# design.net
KiCad netlist of a schematic drawn in Altium Designer
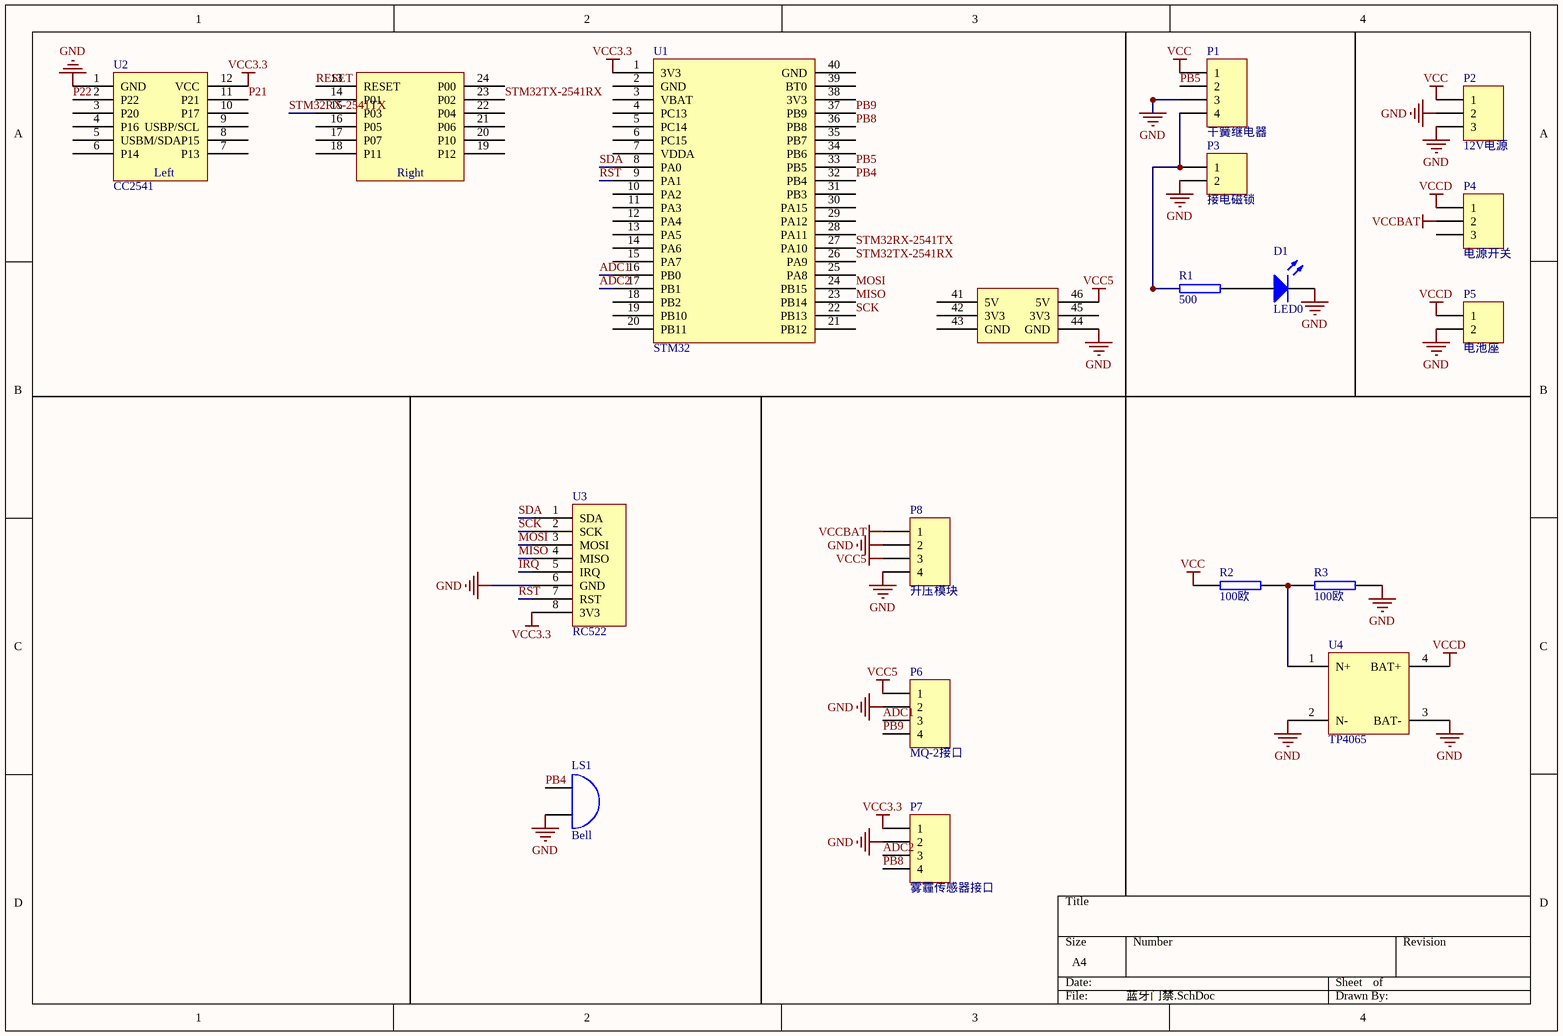
[diagram p0: 蓝牙门禁.SchDoc]

(export (version "E")
  (design (tool "Eeschema 10.0.6"))
  (components
    (comp (ref "D1")
      (value "LED0")
      (footprint "0805-led")
      (description "Typical INFRARED GaAs LED")
      (fields (field (name "PUBLISHER") "Altium Limited"))
      (libsource (lib "Miscellaneous Devices") (part "LED0"))
    )
    (comp (ref "LS1")
      (value "Bell")
      (footprint "BUZZER-12MM")
      (description "Electrical Bell")
      (fields (field (name "PUBLISHER") "Altium Limited"))
      (libsource (lib "Miscellaneous Devices") (part "Bell"))
    )
    (comp (ref "P1")
      (value "干簧继电器")
      (footprint "干簧继电器SIP-1A05")
      (description "Header, 4-Pin")
      (fields (field (name "PUBLISHER") "Altium Limited"))
      (libsource (lib "Miscellaneous Connectors") (part "Header 4"))
    )
    (comp (ref "P2")
      (value "12V电源")
      (footprint "DC-005(5.5MM)")
      (description "Header, 3-Pin")
      (fields (field (name "PUBLISHER") "Altium Limited"))
      (libsource (lib "Miscellaneous Connectors") (part "Header 3"))
    )
    (comp (ref "P3")
      (value "接电磁锁")
      (footprint "接线端子-0.5")
      (description "Header, 2-Pin, Right Angle")
      (fields (field (name "PUBLISHER") "Altium Limited"))
      (libsource (lib "Miscellaneous Connectors") (part "Header 2H"))
    )
    (comp (ref "P4")
      (value "电源开关")
      (footprint "拨动开关（2mm）")
      (description "Header, 3-Pin")
      (fields (field (name "PUBLISHER") "Altium Limited"))
      (libsource (lib "Miscellaneous Connectors") (part "Header 3"))
    )
    (comp (ref "P5")
      (value "电池座")
      (footprint "7号电池盒-4.5CM")
      (description "Header, 2-Pin")
      (fields (field (name "PUBLISHER") "Altium Limited"))
      (libsource (lib "Miscellaneous Connectors") (part "Header 2"))
    )
    (comp (ref "P6")
      (value "MQ-2接口")
      (footprint "HDR1X4")
      (description "Header, 4-Pin")
      (fields (field (name "PUBLISHER") "Altium Limited"))
      (libsource (lib "Miscellaneous Connectors") (part "Header 4"))
    )
    (comp (ref "P7")
      (value "雾霾传感器接口")
      (footprint "HDR1X4")
      (description "Header, 4-Pin")
      (fields (field (name "PUBLISHER") "Altium Limited"))
      (libsource (lib "Miscellaneous Connectors") (part "Header 4"))
    )
    (comp (ref "P8")
      (value "升压模块")
      (footprint "DC-DC升压模块")
      (description "Header, 4-Pin")
      (fields (field (name "PUBLISHER") "Altium Limited"))
      (libsource (lib "Miscellaneous Connectors") (part "Header 4"))
    )
    (comp (ref "R1") (value "500") (footprint "0805-SMALL") (libsource (lib "CC254xEM原理图库") (part "RES2")))
    (comp (ref "R2") (value "100欧") (footprint "0805-SMALL") (libsource (lib "CC254xEM原理图库") (part "RES2")))
    (comp (ref "R3") (value "100欧") (footprint "0805-SMALL") (libsource (lib "CC254xEM原理图库") (part "RES2")))
    (comp (ref "U1") (value "STM32") (footprint "STM32_Smart") (libsource (lib "我的原理图") (part "STM32_Smart")))
    (comp (ref "U2")
      (value "CC2541")
      (footprint "Smart_RF_2541")
      (libsource (lib "我的原理图") (part "Smart_RF_2541"))
    )
    (comp (ref "U3") (value "RC522") (footprint "HDR1X8") (libsource (lib "我的原理图") (part "RFID_RC522")))
    (comp (ref "U4") (value "TP4065") (footprint "TP4065_模块") (libsource (lib "我的原理图") (part "TP4056_ 模块")))
  )
  (nets
    (net (code "1") (name "/ADC1") (class "Default")
      (node (ref "P6") (pin "3") (pinfunction "3_3") (pintype "passive"))
      (node (ref "U1") (pin "16") (pinfunction "PB0_16") (pintype "passive"))
    )
    (net (code "2") (name "/ADC2") (class "Default")
      (node (ref "P7") (pin "3") (pinfunction "3_3") (pintype "passive"))
      (node (ref "U1") (pin "17") (pinfunction "PB1_17") (pintype "passive"))
    )
    (net (code "3") (name "/IRQ") (class "Default")
      (node (ref "U3") (pin "5") (pinfunction "IRQ_5") (pintype "passive"))
    )
    (net (code "4") (name "/MISO") (class "Default")
      (node (ref "U1") (pin "23") (pinfunction "PB14_23") (pintype "passive"))
      (node (ref "U3") (pin "4") (pinfunction "MISO_4") (pintype "passive"))
    )
    (net (code "5") (name "/MOSI") (class "Default")
      (node (ref "U1") (pin "24") (pinfunction "PB15_24") (pintype "passive"))
      (node (ref "U3") (pin "3") (pinfunction "MOSI_3") (pintype "passive"))
    )
    (net (code "6") (name "/P21") (class "Default")
      (node (ref "U2") (pin "11") (pinfunction "P21_11") (pintype "passive"))
    )
    (net (code "7") (name "/P22") (class "Default")
      (node (ref "U2") (pin "2") (pinfunction "P22_2") (pintype "passive"))
    )
    (net (code "8") (name "/PB4") (class "Default")
      (node (ref "LS1") (pin "1") (pinfunction "A_1") (pintype "passive"))
      (node (ref "U1") (pin "32") (pinfunction "PB4_32") (pintype "passive"))
    )
    (net (code "9") (name "/PB5") (class "Default")
      (node (ref "P1") (pin "2") (pinfunction "2_2") (pintype "passive"))
      (node (ref "U1") (pin "33") (pinfunction "PB5_33") (pintype "passive"))
    )
    (net (code "10") (name "/PB8") (class "Default")
      (node (ref "P7") (pin "4") (pinfunction "4_4") (pintype "passive"))
      (node (ref "U1") (pin "36") (pinfunction "PB8_36") (pintype "passive"))
    )
    (net (code "11") (name "/PB9") (class "Default")
      (node (ref "P6") (pin "4") (pinfunction "4_4") (pintype "passive"))
      (node (ref "U1") (pin "37") (pinfunction "PB9_37") (pintype "passive"))
    )
    (net (code "12") (name "/RESET") (class "Default")
      (node (ref "U2") (pin "13") (pinfunction "RESET_13") (pintype "passive"))
    )
    (net (code "13") (name "/RST") (class "Default")
      (node (ref "U1") (pin "9") (pinfunction "PA1_9") (pintype "passive"))
      (node (ref "U3") (pin "7") (pinfunction "RST_7") (pintype "passive"))
    )
    (net (code "14") (name "/SCK") (class "Default")
      (node (ref "U1") (pin "22") (pinfunction "PB13_22") (pintype "passive"))
      (node (ref "U3") (pin "2") (pinfunction "SCK_2") (pintype "passive"))
    )
    (net (code "15") (name "/SDA") (class "Default")
      (node (ref "U1") (pin "8") (pinfunction "PA0_8") (pintype "passive"))
      (node (ref "U3") (pin "1") (pinfunction "SDA_1") (pintype "passive"))
    )
    (net (code "16") (name "/STM32RX-2541TX") (class "Default")
      (node (ref "U1") (pin "27") (pinfunction "PA10_27") (pintype "passive"))
      (node (ref "U2") (pin "15") (pinfunction "P03_15") (pintype "passive"))
    )
    (net (code "17") (name "/STM32TX-2541RX") (class "Default")
      (node (ref "U1") (pin "26") (pinfunction "PA9_26") (pintype "passive"))
      (node (ref "U2") (pin "23") (pinfunction "P02_23") (pintype "passive"))
    )
    (net (code "18") (name "GND") (class "Default")
      (node (ref "D1") (pin "2") (pinfunction "K_2") (pintype "passive"))
      (node (ref "LS1") (pin "2") (pinfunction "B_2") (pintype "passive"))
      (node (ref "P1") (pin "3") (pinfunction "3_3") (pintype "passive"))
      (node (ref "P2") (pin "2") (pinfunction "2_2") (pintype "passive"))
      (node (ref "P2") (pin "3") (pinfunction "3_3") (pintype "passive"))
      (node (ref "P3") (pin "2") (pinfunction "2_2") (pintype "passive"))
      (node (ref "P5") (pin "2") (pinfunction "2_2") (pintype "passive"))
      (node (ref "P6") (pin "2") (pinfunction "2_2") (pintype "passive"))
      (node (ref "P7") (pin "2") (pinfunction "2_2") (pintype "passive"))
      (node (ref "P8") (pin "2") (pinfunction "2_2") (pintype "passive"))
      (node (ref "P8") (pin "4") (pinfunction "4_4") (pintype "passive"))
      (node (ref "R3") (pin "2") (pinfunction "2_2") (pintype "passive"))
      (node (ref "U1") (pin "44") (pinfunction "GND_44") (pintype "passive"))
      (node (ref "U2") (pin "1") (pinfunction "GND_1") (pintype "passive"))
      (node (ref "U3") (pin "6") (pinfunction "GND_6") (pintype "passive"))
      (node (ref "U4") (pin "2") (pinfunction "N-_2") (pintype "passive"))
      (node (ref "U4") (pin "3") (pinfunction "BAT-_3") (pintype "passive"))
    )
    (net (code "19") (name "Net-(D1-A)") (class "Default")
      (node (ref "D1") (pin "1") (pinfunction "A_1") (pintype "passive"))
      (node (ref "R1") (pin "2") (pinfunction "2_2") (pintype "passive"))
    )
    (net (code "20") (name "Net-(P1-Pad4)") (class "Default")
      (node (ref "P1") (pin "4") (pinfunction "4_4") (pintype "passive"))
      (node (ref "P3") (pin "1") (pinfunction "1_1") (pintype "passive"))
      (node (ref "R1") (pin "1") (pinfunction "1_1") (pintype "passive"))
    )
    (net (code "21") (name "Net-(U4-N+)") (class "Default")
      (node (ref "R2") (pin "2") (pinfunction "2_2") (pintype "passive"))
      (node (ref "R3") (pin "1") (pinfunction "1_1") (pintype "passive"))
      (node (ref "U4") (pin "1") (pinfunction "N+_1") (pintype "passive"))
    )
    (net (code "22") (name "VCC") (class "Default")
      (node (ref "P1") (pin "1") (pinfunction "1_1") (pintype "passive"))
      (node (ref "P2") (pin "1") (pinfunction "1_1") (pintype "passive"))
      (node (ref "R2") (pin "1") (pinfunction "1_1") (pintype "passive"))
    )
    (net (code "23") (name "VCC3.3") (class "Default")
      (node (ref "P7") (pin "1") (pinfunction "1_1") (pintype "passive"))
      (node (ref "U1") (pin "1") (pinfunction "3V3_1") (pintype "passive"))
      (node (ref "U2") (pin "12") (pinfunction "VCC_12") (pintype "passive"))
      (node (ref "U3") (pin "8") (pinfunction "3V3_8") (pintype "passive"))
    )
    (net (code "24") (name "VCC5") (class "Default")
      (node (ref "P6") (pin "1") (pinfunction "1_1") (pintype "passive"))
      (node (ref "P8") (pin "3") (pinfunction "3_3") (pintype "passive"))
      (node (ref "U1") (pin "46") (pinfunction "5V_46") (pintype "passive"))
    )
    (net (code "25") (name "VCCBAT") (class "Default")
      (node (ref "P4") (pin "2") (pinfunction "2_2") (pintype "passive"))
      (node (ref "P8") (pin "1") (pinfunction "1_1") (pintype "passive"))
    )
    (net (code "26") (name "VCCD") (class "Default")
      (node (ref "P4") (pin "1") (pinfunction "1_1") (pintype "passive"))
      (node (ref "P5") (pin "1") (pinfunction "1_1") (pintype "passive"))
      (node (ref "U4") (pin "4") (pinfunction "BAT+_4") (pintype "passive"))
    )
    (net (code "27") (name "unconnected-(P4-Pad3)") (class "Default")
      (node (ref "P4") (pin "3") (pinfunction "3_3") (pintype "passive"))
    )
    (net (code "28") (name "unconnected-(U1-3V3-Pad38)") (class "Default")
      (node (ref "U1") (pin "38") (pinfunction "3V3_38") (pintype "passive"))
    )
    (net (code "29") (name "unconnected-(U1-3V3-Pad42)") (class "Default")
      (node (ref "U1") (pin "42") (pinfunction "3V3_42") (pintype "passive"))
    )
    (net (code "30") (name "unconnected-(U1-3V3-Pad45)") (class "Default")
      (node (ref "U1") (pin "45") (pinfunction "3V3_45") (pintype "passive"))
    )
    (net (code "31") (name "unconnected-(U1-5V-Pad41)") (class "Default")
      (node (ref "U1") (pin "41") (pinfunction "5V_41") (pintype "passive"))
    )
    (net (code "32") (name "unconnected-(U1-BT0-Pad39)") (class "Default")
      (node (ref "U1") (pin "39") (pinfunction "BT0_39") (pintype "passive"))
    )
    (net (code "33") (name "unconnected-(U1-GND-Pad2)") (class "Default")
      (node (ref "U1") (pin "2") (pinfunction "GND_2") (pintype "passive"))
    )
    (net (code "34") (name "unconnected-(U1-GND-Pad40)") (class "Default")
      (node (ref "U1") (pin "40") (pinfunction "GND_40") (pintype "passive"))
    )
    (net (code "35") (name "unconnected-(U1-GND-Pad43)") (class "Default")
      (node (ref "U1") (pin "43") (pinfunction "GND_43") (pintype "passive"))
    )
    (net (code "36") (name "unconnected-(U1-PA2-Pad10)") (class "Default")
      (node (ref "U1") (pin "10") (pinfunction "PA2_10") (pintype "passive"))
    )
    (net (code "37") (name "unconnected-(U1-PA3-Pad11)") (class "Default")
      (node (ref "U1") (pin "11") (pinfunction "PA3_11") (pintype "passive"))
    )
    (net (code "38") (name "unconnected-(U1-PA4-Pad12)") (class "Default")
      (node (ref "U1") (pin "12") (pinfunction "PA4_12") (pintype "passive"))
    )
    (net (code "39") (name "unconnected-(U1-PA5-Pad13)") (class "Default")
      (node (ref "U1") (pin "13") (pinfunction "PA5_13") (pintype "passive"))
    )
    (net (code "40") (name "unconnected-(U1-PA6-Pad14)") (class "Default")
      (node (ref "U1") (pin "14") (pinfunction "PA6_14") (pintype "passive"))
    )
    (net (code "41") (name "unconnected-(U1-PA7-Pad15)") (class "Default")
      (node (ref "U1") (pin "15") (pinfunction "PA7_15") (pintype "passive"))
    )
    (net (code "42") (name "unconnected-(U1-PA8-Pad25)") (class "Default")
      (node (ref "U1") (pin "25") (pinfunction "PA8_25") (pintype "passive"))
    )
    (net (code "43") (name "unconnected-(U1-PA11-Pad28)") (class "Default")
      (node (ref "U1") (pin "28") (pinfunction "PA11_28") (pintype "passive"))
    )
    (net (code "44") (name "unconnected-(U1-PA12-Pad29)") (class "Default")
      (node (ref "U1") (pin "29") (pinfunction "PA12_29") (pintype "passive"))
    )
    (net (code "45") (name "unconnected-(U1-PA15-Pad30)") (class "Default")
      (node (ref "U1") (pin "30") (pinfunction "PA15_30") (pintype "passive"))
    )
    (net (code "46") (name "unconnected-(U1-PB2-Pad18)") (class "Default")
      (node (ref "U1") (pin "18") (pinfunction "PB2_18") (pintype "passive"))
    )
    (net (code "47") (name "unconnected-(U1-PB3-Pad31)") (class "Default")
      (node (ref "U1") (pin "31") (pinfunction "PB3_31") (pintype "passive"))
    )
    (net (code "48") (name "unconnected-(U1-PB6-Pad34)") (class "Default")
      (node (ref "U1") (pin "34") (pinfunction "PB6_34") (pintype "passive"))
    )
    (net (code "49") (name "unconnected-(U1-PB7-Pad35)") (class "Default")
      (node (ref "U1") (pin "35") (pinfunction "PB7_35") (pintype "passive"))
    )
    (net (code "50") (name "unconnected-(U1-PB10-Pad19)") (class "Default")
      (node (ref "U1") (pin "19") (pinfunction "PB10_19") (pintype "passive"))
    )
    (net (code "51") (name "unconnected-(U1-PB11-Pad20)") (class "Default")
      (node (ref "U1") (pin "20") (pinfunction "PB11_20") (pintype "passive"))
    )
    (net (code "52") (name "unconnected-(U1-PB12-Pad21)") (class "Default")
      (node (ref "U1") (pin "21") (pinfunction "PB12_21") (pintype "passive"))
    )
    (net (code "53") (name "unconnected-(U1-PC13-Pad4)") (class "Default")
      (node (ref "U1") (pin "4") (pinfunction "PC13_4") (pintype "passive"))
    )
    (net (code "54") (name "unconnected-(U1-PC14-Pad5)") (class "Default")
      (node (ref "U1") (pin "5") (pinfunction "PC14_5") (pintype "passive"))
    )
    (net (code "55") (name "unconnected-(U1-PC15-Pad6)") (class "Default")
      (node (ref "U1") (pin "6") (pinfunction "PC15_6") (pintype "passive"))
    )
    (net (code "56") (name "unconnected-(U1-VBAT-Pad3)") (class "Default")
      (node (ref "U1") (pin "3") (pinfunction "VBAT_3") (pintype "passive"))
    )
    (net (code "57") (name "unconnected-(U1-VDDA-Pad7)") (class "Default")
      (node (ref "U1") (pin "7") (pinfunction "VDDA_7") (pintype "passive"))
    )
    (net (code "58") (name "unconnected-(U2-P00-Pad24)") (class "Default")
      (node (ref "U2") (pin "24") (pinfunction "P00_24") (pintype "passive"))
    )
    (net (code "59") (name "unconnected-(U2-P01-Pad14)") (class "Default")
      (node (ref "U2") (pin "14") (pinfunction "P01_14") (pintype "passive"))
    )
    (net (code "60") (name "unconnected-(U2-P04-Pad22)") (class "Default")
      (node (ref "U2") (pin "22") (pinfunction "P04_22") (pintype "passive"))
    )
    (net (code "61") (name "unconnected-(U2-P05-Pad16)") (class "Default")
      (node (ref "U2") (pin "16") (pinfunction "P05_16") (pintype "passive"))
    )
    (net (code "62") (name "unconnected-(U2-P06-Pad21)") (class "Default")
      (node (ref "U2") (pin "21") (pinfunction "P06_21") (pintype "passive"))
    )
    (net (code "63") (name "unconnected-(U2-P07-Pad17)") (class "Default")
      (node (ref "U2") (pin "17") (pinfunction "P07_17") (pintype "passive"))
    )
    (net (code "64") (name "unconnected-(U2-P10-Pad20)") (class "Default")
      (node (ref "U2") (pin "20") (pinfunction "P10_20") (pintype "passive"))
    )
    (net (code "65") (name "unconnected-(U2-P11-Pad18)") (class "Default")
      (node (ref "U2") (pin "18") (pinfunction "P11_18") (pintype "passive"))
    )
    (net (code "66") (name "unconnected-(U2-P12-Pad19)") (class "Default")
      (node (ref "U2") (pin "19") (pinfunction "P12_19") (pintype "passive"))
    )
    (net (code "67") (name "unconnected-(U2-P13-Pad7)") (class "Default")
      (node (ref "U2") (pin "7") (pinfunction "P13_7") (pintype "passive"))
    )
    (net (code "68") (name "unconnected-(U2-P14-Pad6)") (class "Default")
      (node (ref "U2") (pin "6") (pinfunction "P14_6") (pintype "passive"))
    )
    (net (code "69") (name "unconnected-(U2-P15-Pad8)") (class "Default")
      (node (ref "U2") (pin "8") (pinfunction "P15_8") (pintype "passive"))
    )
    (net (code "70") (name "unconnected-(U2-P16-Pad4)") (class "Default")
      (node (ref "U2") (pin "4") (pinfunction "P16_4") (pintype "passive"))
    )
    (net (code "71") (name "unconnected-(U2-P17-Pad10)") (class "Default")
      (node (ref "U2") (pin "10") (pinfunction "P17_10") (pintype "passive"))
    )
    (net (code "72") (name "unconnected-(U2-P20-Pad3)") (class "Default")
      (node (ref "U2") (pin "3") (pinfunction "P20_3") (pintype "passive"))
    )
    (net (code "73") (name "unconnected-(U2-USBM{slash}SDA-Pad5)") (class "Default")
      (node (ref "U2") (pin "5") (pinfunction "USBM/SDA_5") (pintype "passive"))
    )
    (net (code "74") (name "unconnected-(U2-USBP{slash}SCL-Pad9)") (class "Default")
      (node (ref "U2") (pin "9") (pinfunction "USBP/SCL_9") (pintype "passive"))
    )
  )
)
